# MKR2UNO.net
KiCad netlist of a schematic drawn in EAGLE
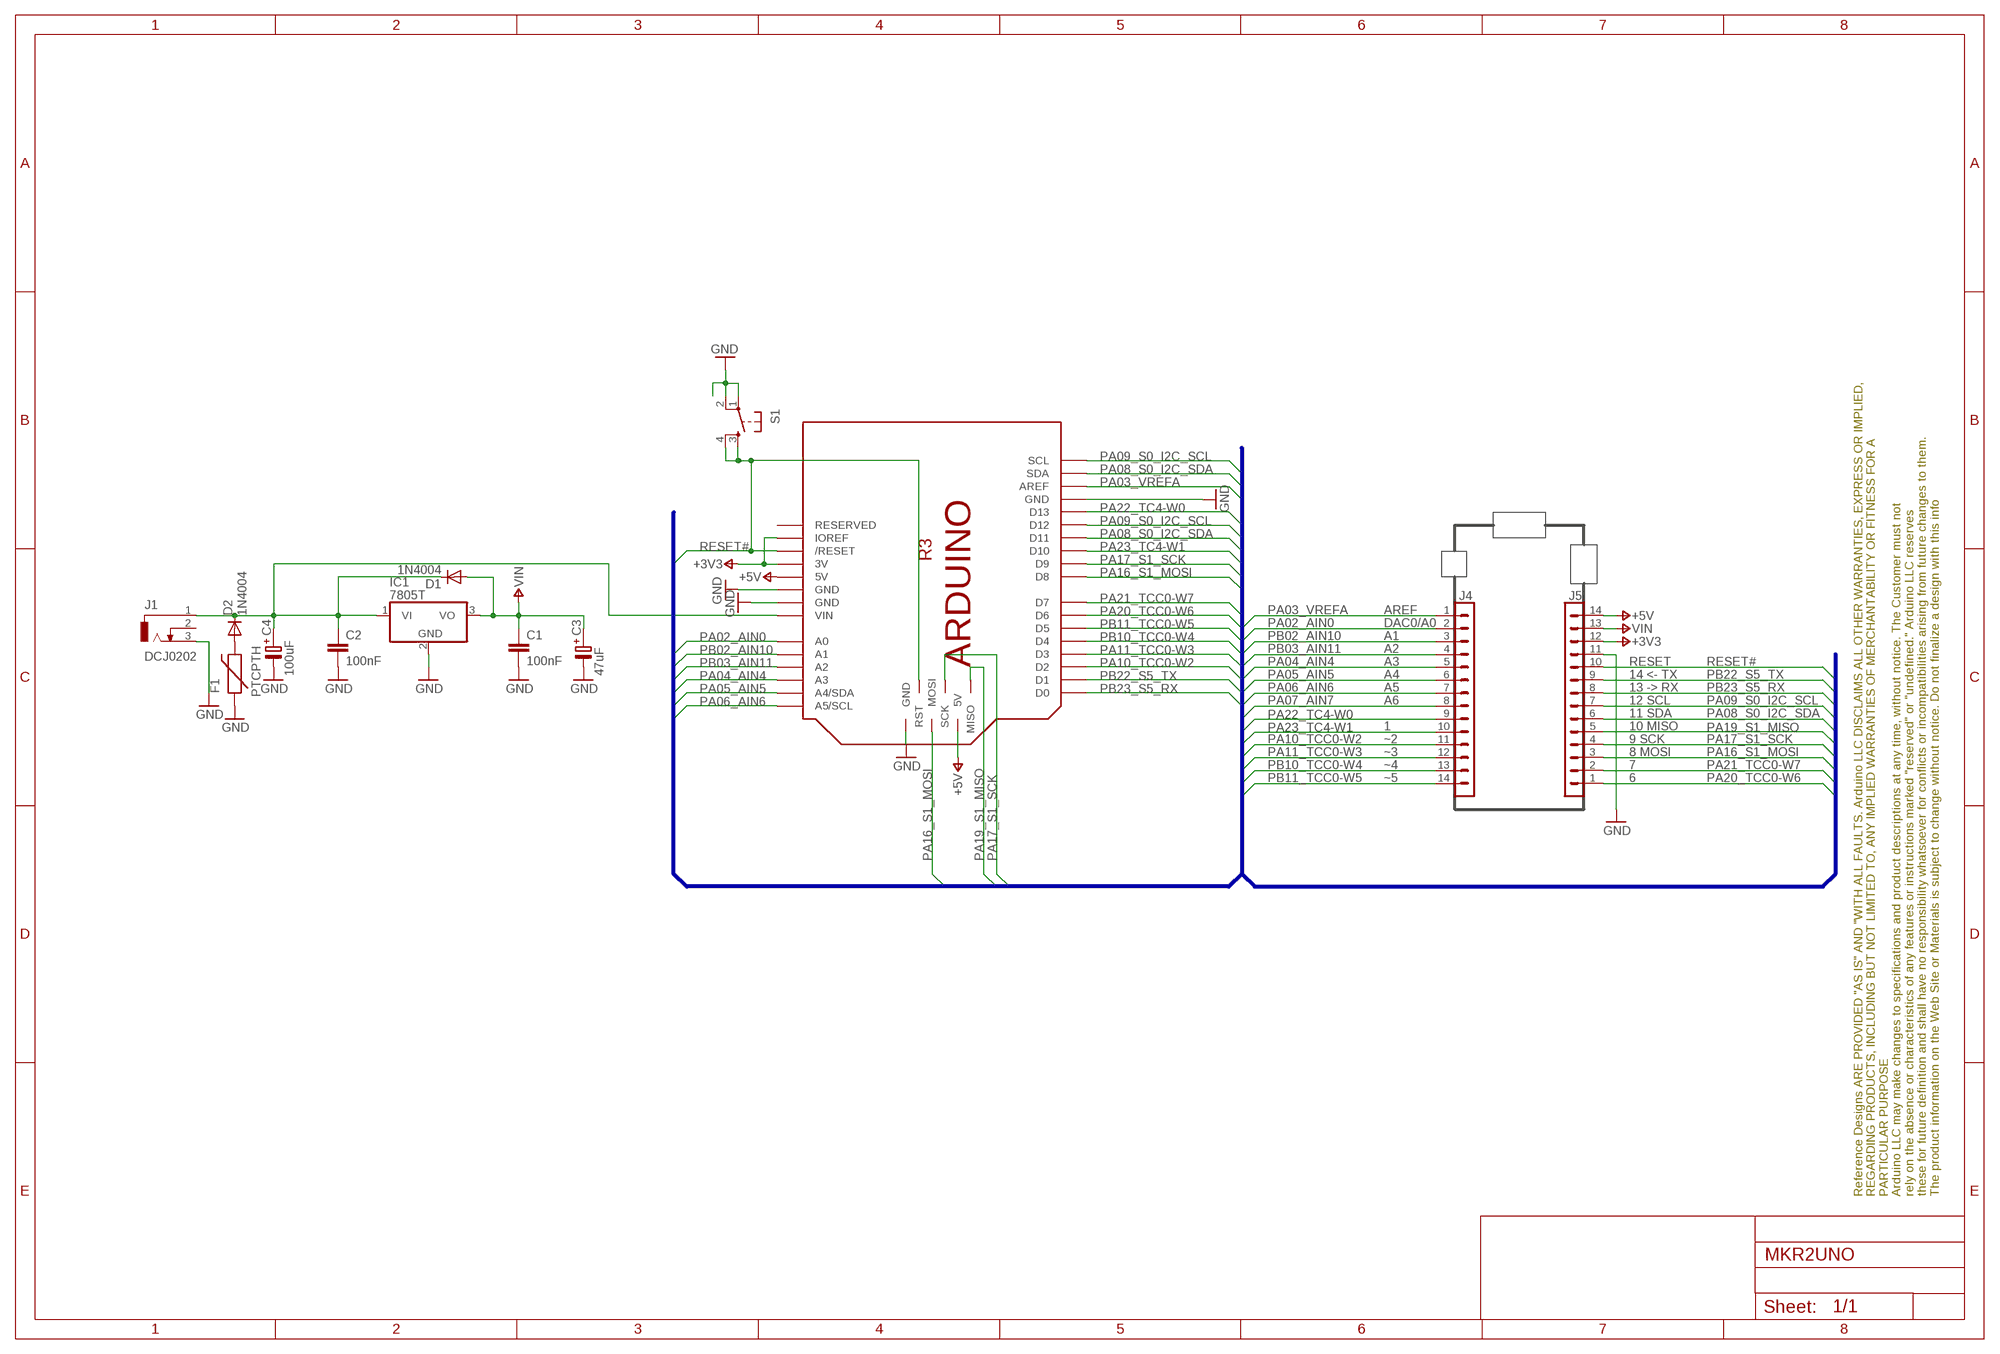
[diagram p0: schematic, sheet 1]

(export (version "E")
  (design (tool "Eeschema 10.0.6"))
  (components
    (comp (ref "C1")
      (value "100nF")
      (footprint "eagle-import:C025-024X044")
      (libsource (lib "eagle-import") (part "C-EU025-024X044"))
    )
    (comp (ref "C2")
      (value "100nF")
      (footprint "eagle-import:C025-024X044")
      (libsource (lib "eagle-import") (part "C-EU025-024X044"))
    )
    (comp (ref "C3")
      (value "47uF")
      (footprint "eagle-import:EA6,3-10")
      (libsource (lib "eagle-import") (part "C-PA-6,3X10"))
    )
    (comp (ref "C4")
      (value "100uF")
      (footprint "eagle-import:EA6,3-10")
      (libsource (lib "eagle-import") (part "C-PA-6,3X10"))
    )
    (comp (ref "D1")
      (value "1N4004")
      (footprint "eagle-import:DO41-10")
      (libsource (lib "eagle-import") (part "1N4004"))
    )
    (comp (ref "D2")
      (value "1N4004")
      (footprint "eagle-import:DO41-10")
      (libsource (lib "eagle-import") (part "1N4004"))
    )
    (comp (ref "F1")
      (value "PTCPTH")
      (footprint "eagle-import:PTC")
      (libsource (lib "eagle-import") (part "PTCPTH"))
    )
    (comp (ref "FRAME1")
      (value "Page 1")
      (footprint "eagle-import:FRAME")
      (libsource (lib "eagle-import") (part "A3L-LOC"))
    )
    (comp (ref "IC1")
      (value "7805T")
      (footprint "eagle-import:TO220H")
      (libsource (lib "eagle-import") (part "78T05"))
    )
    (comp (ref "J1")
      (value "DCJ0202")
      (footprint "eagle-import:DCJ0202")
      (libsource (lib "eagle-import") (part "DCJ0202"))
    )
    (comp (ref "J4")
      (value "DNP")
      (footprint "eagle-import:1X14")
      (libsource (lib "eagle-import") (part "STRIP-14STD"))
    )
    (comp (ref "J5")
      (value "DNP")
      (footprint "eagle-import:1X14")
      (libsource (lib "eagle-import") (part "STRIP-14STD"))
    )
    (comp (ref "M1")
      (value "ARDUINO_R3_ICSP")
      (footprint "eagle-import:ARDUINOR3_ICSP")
      (libsource (lib "eagle-import") (part "ARDUINO_R3_ICSP"))
    )
    (comp (ref "S1")
      (value "TAC_SWITCHPTH")
      (footprint "eagle-import:TACTILE-PTH")
      (libsource (lib "eagle-import") (part "TAC_SWITCHPTH"))
    )
  )
  (nets
    (net (code "1") (name "+3V3") (class "Default")
      (node (ref "J5") (pin "12") (pinfunction "12_12") (pintype "passive"))
      (node (ref "M1") (pin "3V") (pinfunction "3V_3V") (pintype "power_in"))
      (node (ref "M1") (pin "IOREF") (pinfunction "IOREF_IOREF") (pintype "output"))
    )
    (net (code "2") (name "+5V") (class "Default")
      (node (ref "J5") (pin "14") (pinfunction "14_14") (pintype "passive"))
      (node (ref "M1") (pin "5V") (pinfunction "5V_5V") (pintype "power_in"))
      (node (ref "M1") (pin "5V_ICSP") (pinfunction "5V_5V_ICSP") (pintype "passive"))
    )
    (net (code "3") (name "/PA02_AIN0") (class "Default")
      (node (ref "J4") (pin "2") (pinfunction "2_2") (pintype "passive"))
      (node (ref "M1") (pin "A0") (pinfunction "A0_A0") (pintype "bidirectional"))
    )
    (net (code "4") (name "/PA03_VREFA") (class "Default")
      (node (ref "J4") (pin "1") (pinfunction "1_1") (pintype "passive"))
      (node (ref "M1") (pin "AREF") (pinfunction "AREF_AREF") (pintype "bidirectional"))
    )
    (net (code "5") (name "/PA04_AIN4") (class "Default")
      (node (ref "J4") (pin "5") (pinfunction "5_5") (pintype "passive"))
      (node (ref "M1") (pin "A3") (pinfunction "A3_A3") (pintype "bidirectional"))
    )
    (net (code "6") (name "/PA05_AIN5") (class "Default")
      (node (ref "J4") (pin "6") (pinfunction "6_6") (pintype "passive"))
      (node (ref "M1") (pin "A4") (pinfunction "A4/SDA_A4") (pintype "bidirectional"))
    )
    (net (code "7") (name "/PA06_AIN6") (class "Default")
      (node (ref "J4") (pin "7") (pinfunction "7_7") (pintype "passive"))
      (node (ref "M1") (pin "A5") (pinfunction "A5/SCL_A5") (pintype "bidirectional"))
    )
    (net (code "8") (name "/PA07_AIN7") (class "Default")
      (node (ref "J4") (pin "8") (pinfunction "8_8") (pintype "passive"))
    )
    (net (code "9") (name "/PA08_S0_I2C_SDA") (class "Default")
      (node (ref "J5") (pin "6") (pinfunction "6_6") (pintype "passive"))
      (node (ref "M1") (pin "D11") (pinfunction "D11_D11") (pintype "bidirectional"))
      (node (ref "M1") (pin "SDA") (pinfunction "SDA_SDA") (pintype "bidirectional"))
    )
    (net (code "10") (name "/PA09_S0_I2C_SCL") (class "Default")
      (node (ref "J5") (pin "7") (pinfunction "7_7") (pintype "passive"))
      (node (ref "M1") (pin "D12") (pinfunction "D12_D12") (pintype "bidirectional"))
      (node (ref "M1") (pin "SCL") (pinfunction "SCL_SCL") (pintype "bidirectional"))
    )
    (net (code "11") (name "/PA10_TCC0-W2") (class "Default")
      (node (ref "J4") (pin "11") (pinfunction "11_11") (pintype "passive"))
      (node (ref "M1") (pin "D2") (pinfunction "D2_D2") (pintype "bidirectional"))
    )
    (net (code "12") (name "/PA11_TCC0-W3") (class "Default")
      (node (ref "J4") (pin "12") (pinfunction "12_12") (pintype "passive"))
      (node (ref "M1") (pin "D3") (pinfunction "D3_D3") (pintype "bidirectional"))
    )
    (net (code "13") (name "/PA16_S1_MOSI") (class "Default")
      (node (ref "J5") (pin "3") (pinfunction "3_3") (pintype "passive"))
      (node (ref "M1") (pin "D8") (pinfunction "D8_D8") (pintype "bidirectional"))
      (node (ref "M1") (pin "MOSI") (pinfunction "MOSI_MOSI") (pintype "passive"))
    )
    (net (code "14") (name "/PA17_S1_SCK") (class "Default")
      (node (ref "J5") (pin "4") (pinfunction "4_4") (pintype "passive"))
      (node (ref "M1") (pin "D9") (pinfunction "D9_D9") (pintype "bidirectional"))
      (node (ref "M1") (pin "SCK") (pinfunction "SCK_SCK") (pintype "passive"))
    )
    (net (code "15") (name "/PA19_S1_MISO") (class "Default")
      (node (ref "J5") (pin "5") (pinfunction "5_5") (pintype "passive"))
      (node (ref "M1") (pin "MISO") (pinfunction "MISO_MISO") (pintype "passive"))
    )
    (net (code "16") (name "/PA20_TCC0-W6") (class "Default")
      (node (ref "J5") (pin "1") (pinfunction "1_1") (pintype "passive"))
      (node (ref "M1") (pin "D6") (pinfunction "D6_D6") (pintype "bidirectional"))
    )
    (net (code "17") (name "/PA21_TCC0-W7") (class "Default")
      (node (ref "J5") (pin "2") (pinfunction "2_2") (pintype "passive"))
      (node (ref "M1") (pin "D7") (pinfunction "D7_D7") (pintype "bidirectional"))
    )
    (net (code "18") (name "/PA22_TC4-W0") (class "Default")
      (node (ref "J4") (pin "9") (pinfunction "9_9") (pintype "passive"))
      (node (ref "M1") (pin "D13") (pinfunction "D13_D13") (pintype "bidirectional"))
    )
    (net (code "19") (name "/PA23_TC4-W1") (class "Default")
      (node (ref "J4") (pin "10") (pinfunction "10_10") (pintype "passive"))
      (node (ref "M1") (pin "D10") (pinfunction "D10_D10") (pintype "bidirectional"))
    )
    (net (code "20") (name "/PB02_AIN10") (class "Default")
      (node (ref "J4") (pin "3") (pinfunction "3_3") (pintype "passive"))
      (node (ref "M1") (pin "A1") (pinfunction "A1_A1") (pintype "bidirectional"))
    )
    (net (code "21") (name "/PB03_AIN11") (class "Default")
      (node (ref "J4") (pin "4") (pinfunction "4_4") (pintype "passive"))
      (node (ref "M1") (pin "A2") (pinfunction "A2_A2") (pintype "bidirectional"))
    )
    (net (code "22") (name "/PB10_TCC0-W4") (class "Default")
      (node (ref "J4") (pin "13") (pinfunction "13_13") (pintype "passive"))
      (node (ref "M1") (pin "D4") (pinfunction "D4_D4") (pintype "bidirectional"))
    )
    (net (code "23") (name "/PB11_TCC0-W5") (class "Default")
      (node (ref "J4") (pin "14") (pinfunction "14_14") (pintype "passive"))
      (node (ref "M1") (pin "D5") (pinfunction "D5_D5") (pintype "bidirectional"))
    )
    (net (code "24") (name "/PB22_S5_TX") (class "Default")
      (node (ref "J5") (pin "9") (pinfunction "9_9") (pintype "passive"))
      (node (ref "M1") (pin "D1") (pinfunction "D1_D1") (pintype "bidirectional"))
    )
    (net (code "25") (name "/PB23_S5_RX") (class "Default")
      (node (ref "J5") (pin "8") (pinfunction "8_8") (pintype "passive"))
      (node (ref "M1") (pin "D0") (pinfunction "D0_D0") (pintype "bidirectional"))
    )
    (net (code "26") (name "/RESET#") (class "Default")
      (node (ref "J5") (pin "10") (pinfunction "10_10") (pintype "passive"))
      (node (ref "M1") (pin "RESET") (pinfunction "/RESET_RESET") (pintype "bidirectional"))
      (node (ref "M1") (pin "RESET_ICSP") (pinfunction "RST_RESET_ICSP") (pintype "passive"))
      (node (ref "S1") (pin "3") (pinfunction "3_3") (pintype "passive"))
      (node (ref "S1") (pin "4") (pinfunction "4_4") (pintype "passive"))
    )
    (net (code "27") (name "GND") (class "Default")
      (node (ref "C1") (pin "2") (pinfunction "2_2") (pintype "passive"))
      (node (ref "C2") (pin "2") (pinfunction "2_2") (pintype "passive"))
      (node (ref "C3") (pin "-") (pinfunction "-_-") (pintype "passive"))
      (node (ref "C4") (pin "-") (pinfunction "-_-") (pintype "passive"))
      (node (ref "F1") (pin "P$1") (pinfunction "1_P$1") (pintype "bidirectional"))
      (node (ref "IC1") (pin "2") (pinfunction "GND_2") (pintype "passive"))
      (node (ref "J1") (pin "3") (pinfunction "3_3") (pintype "passive"))
      (node (ref "J5") (pin "11") (pinfunction "11_11") (pintype "passive"))
      (node (ref "M1") (pin "GND") (pinfunction "GND_GND") (pintype "power_in"))
      (node (ref "M1") (pin "GND@1") (pinfunction "GND_GND@1") (pintype "power_in"))
      (node (ref "M1") (pin "GND@2") (pinfunction "GND_GND@2") (pintype "passive"))
      (node (ref "M1") (pin "GND@3") (pinfunction "GND_GND@3") (pintype "power_in"))
      (node (ref "S1") (pin "1") (pinfunction "1_1") (pintype "passive"))
      (node (ref "S1") (pin "2") (pinfunction "2_2") (pintype "passive"))
    )
    (net (code "28") (name "Net-(F1-2)") (class "Default")
      (node (ref "D2") (pin "A") (pinfunction "A_A") (pintype "passive"))
      (node (ref "F1") (pin "P$2") (pinfunction "2_P$2") (pintype "bidirectional"))
    )
    (net (code "29") (name "Net-(IC1-VI)") (class "Default")
      (node (ref "C2") (pin "1") (pinfunction "1_1") (pintype "passive"))
      (node (ref "C4") (pin "+") (pinfunction "+_+") (pintype "passive"))
      (node (ref "D1") (pin "C") (pinfunction "C_C") (pintype "passive"))
      (node (ref "D2") (pin "C") (pinfunction "C_C") (pintype "passive"))
      (node (ref "IC1") (pin "1") (pinfunction "VI_1") (pintype "input"))
      (node (ref "J1") (pin "1") (pinfunction "1_1") (pintype "passive"))
      (node (ref "M1") (pin "VIN") (pinfunction "VIN_VIN") (pintype "power_in"))
    )
    (net (code "30") (name "VIN") (class "Default")
      (node (ref "C1") (pin "1") (pinfunction "1_1") (pintype "passive"))
      (node (ref "C3") (pin "+") (pinfunction "+_+") (pintype "passive"))
      (node (ref "D1") (pin "A") (pinfunction "A_A") (pintype "passive"))
      (node (ref "IC1") (pin "3") (pinfunction "VO_3") (pintype "passive"))
      (node (ref "J5") (pin "13") (pinfunction "13_13") (pintype "passive"))
    )
    (net (code "31") (name "unconnected-(J1-Pad2)") (class "Default")
      (node (ref "J1") (pin "2") (pinfunction "2_2") (pintype "passive"))
    )
    (net (code "32") (name "unconnected-(M1-PadRESERVED)") (class "Default")
      (node (ref "M1") (pin "RESERVED") (pinfunction "RESERVED_RESERVED") (pintype "no_connect"))
    )
  )
)
